# I2C_DRIVER.net
KiCad netlist of a schematic drawn in Altium Designer
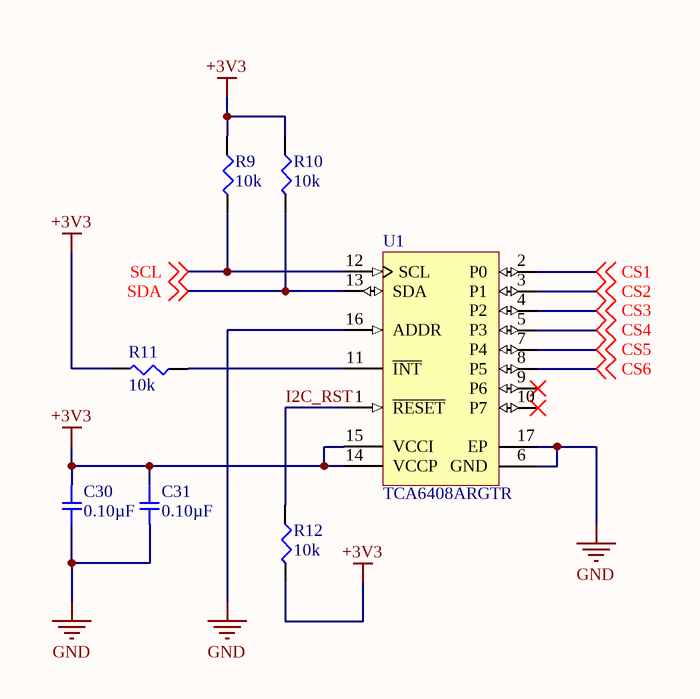
[diagram p0: I2C_DRIVER.SchDoc]

(export (version "E")
  (design (tool "Eeschema 10.0.6"))
  (components
    (comp (ref "C30")
      (value "0.10µF")
      (footprint "SMD-0402C")
      (description "CAP CER 0.1UF 16V X7R 0402")
      (fields
        (field (name "DIGI-KEY PART NUMBER") "490-4759-1-ND")
        (field (name "PART NUMBER") "GCM155R71C104KA55D")
      )
      (libsource (lib "capacitor_murata_0402") (part "GCM155R71C104KA55D"))
    )
    (comp (ref "C31")
      (value "0.10µF")
      (footprint "SMD-0402C")
      (description "CAP CER 0.1UF 16V X7R 0402")
      (fields
        (field (name "DIGI-KEY PART NUMBER") "490-4759-1-ND")
        (field (name "PART NUMBER") "GCM155R71C104KA55D")
      )
      (libsource (lib "capacitor_murata_0402") (part "GCM155R71C104KA55D"))
    )
    (comp (ref "R9")
      (value "10k")
      (footprint "SMD-0402-RES")
      (description "RES SMD 10K OHM 5% 1/10W 0402")
      (fields (field (name "PART NUMBER") "ERJ-2GEJ103X") (field (name "DIGI-KEY PART NUMBER") "P10KJCT-ND"))
      (libsource (lib "Panasonic_ERJ_0402") (part "ERJ-2GEJ103X"))
    )
    (comp (ref "R10")
      (value "10k")
      (footprint "SMD-0402-RES")
      (description "RES SMD 10K OHM 5% 1/10W 0402")
      (fields (field (name "PART NUMBER") "ERJ-2GEJ103X") (field (name "DIGI-KEY PART NUMBER") "P10KJCT-ND"))
      (libsource (lib "Panasonic_ERJ_0402") (part "ERJ-2GEJ103X"))
    )
    (comp (ref "R11")
      (value "10k")
      (footprint "SMD-0402-RES")
      (description "RES SMD 10K OHM 5% 1/10W 0402")
      (fields (field (name "PART NUMBER") "ERJ-2GEJ103X") (field (name "DIGI-KEY PART NUMBER") "P10KJCT-ND"))
      (libsource (lib "Panasonic_ERJ_0402") (part "ERJ-2GEJ103X"))
    )
    (comp (ref "R12")
      (value "10k")
      (footprint "SMD-0402-RES")
      (description "RES SMD 10K OHM 5% 1/10W 0402")
      (fields (field (name "PART NUMBER") "ERJ-2GEJ103X") (field (name "DIGI-KEY PART NUMBER") "P10KJCT-ND"))
      (libsource (lib "Panasonic_ERJ_0402") (part "ERJ-2GEJ103X"))
    )
    (comp (ref "U1")
      (value "TCA6408ARGTR")
      (footprint "RGT0016A_V")
      (fields (field (name "MANUFACTURER") "Texas Instruments"))
      (libsource (lib "Altium Content Vault") (part "TI-TCA6408A-QFN_RGT-16"))
    )
  )
  (nets
    (net (code "1") (name "+3V3") (class "Default")
      (node (ref "C30") (pin "1") (pinfunction "1_1") (pintype "passive"))
      (node (ref "C31") (pin "1") (pinfunction "1_1") (pintype "passive"))
      (node (ref "R10") (pin "1") (pinfunction "1_1") (pintype "passive"))
      (node (ref "R11") (pin "2") (pinfunction "2_2") (pintype "passive"))
      (node (ref "R12") (pin "2") (pinfunction "2_2") (pintype "passive"))
      (node (ref "R9") (pin "1") (pinfunction "1_1") (pintype "passive"))
      (node (ref "U1") (pin "14") (pinfunction "VCCP_14") (pintype "power_in"))
      (node (ref "U1") (pin "15") (pinfunction "VCCI_15") (pintype "power_in"))
    )
    (net (code "2") (name "/I2C_RST") (class "Default")
      (node (ref "R12") (pin "1") (pinfunction "1_1") (pintype "passive"))
      (node (ref "U1") (pin "1") (pinfunction "~{RESET}_1") (pintype "input"))
    )
    (net (code "3") (name "CS1") (class "Default")
      (node (ref "U1") (pin "2") (pinfunction "P0_2") (pintype "bidirectional"))
    )
    (net (code "4") (name "CS2") (class "Default")
      (node (ref "U1") (pin "3") (pinfunction "P1_3") (pintype "bidirectional"))
    )
    (net (code "5") (name "CS3") (class "Default")
      (node (ref "U1") (pin "4") (pinfunction "P2_4") (pintype "bidirectional"))
    )
    (net (code "6") (name "CS4") (class "Default")
      (node (ref "U1") (pin "5") (pinfunction "P3_5") (pintype "bidirectional"))
    )
    (net (code "7") (name "CS5") (class "Default")
      (node (ref "U1") (pin "7") (pinfunction "P4_7") (pintype "bidirectional"))
    )
    (net (code "8") (name "CS6") (class "Default")
      (node (ref "U1") (pin "8") (pinfunction "P5_8") (pintype "bidirectional"))
    )
    (net (code "9") (name "GND") (class "Default")
      (node (ref "C30") (pin "2") (pinfunction "2_2") (pintype "passive"))
      (node (ref "C31") (pin "2") (pinfunction "2_2") (pintype "passive"))
      (node (ref "U1") (pin "16") (pinfunction "ADDR_16") (pintype "input"))
      (node (ref "U1") (pin "17") (pinfunction "EP_17") (pintype "passive"))
      (node (ref "U1") (pin "6") (pinfunction "GND_6") (pintype "power_in"))
    )
    (net (code "10") (name "Net-(U1-~{INT})") (class "Default")
      (node (ref "R11") (pin "1") (pinfunction "1_1") (pintype "passive"))
      (node (ref "U1") (pin "11") (pinfunction "~{INT}_11") (pintype "open_collector"))
    )
    (net (code "11") (name "SCL") (class "Default")
      (node (ref "R9") (pin "2") (pinfunction "2_2") (pintype "passive"))
      (node (ref "U1") (pin "12") (pinfunction "SCL_12") (pintype "input"))
    )
    (net (code "12") (name "SDA") (class "Default")
      (node (ref "R10") (pin "2") (pinfunction "2_2") (pintype "passive"))
      (node (ref "U1") (pin "13") (pinfunction "SDA_13") (pintype "bidirectional"))
    )
    (net (code "13") (name "unconnected-(U1-P6-Pad9)") (class "Default")
      (node (ref "U1") (pin "9") (pinfunction "P6_9") (pintype "bidirectional+no_connect"))
    )
    (net (code "14") (name "unconnected-(U1-P7-Pad10)") (class "Default")
      (node (ref "U1") (pin "10") (pinfunction "P7_10") (pintype "bidirectional+no_connect"))
    )
  )
)
